# LM393_universal_breakout.net
KiCad netlist of a schematic drawn in EAGLE
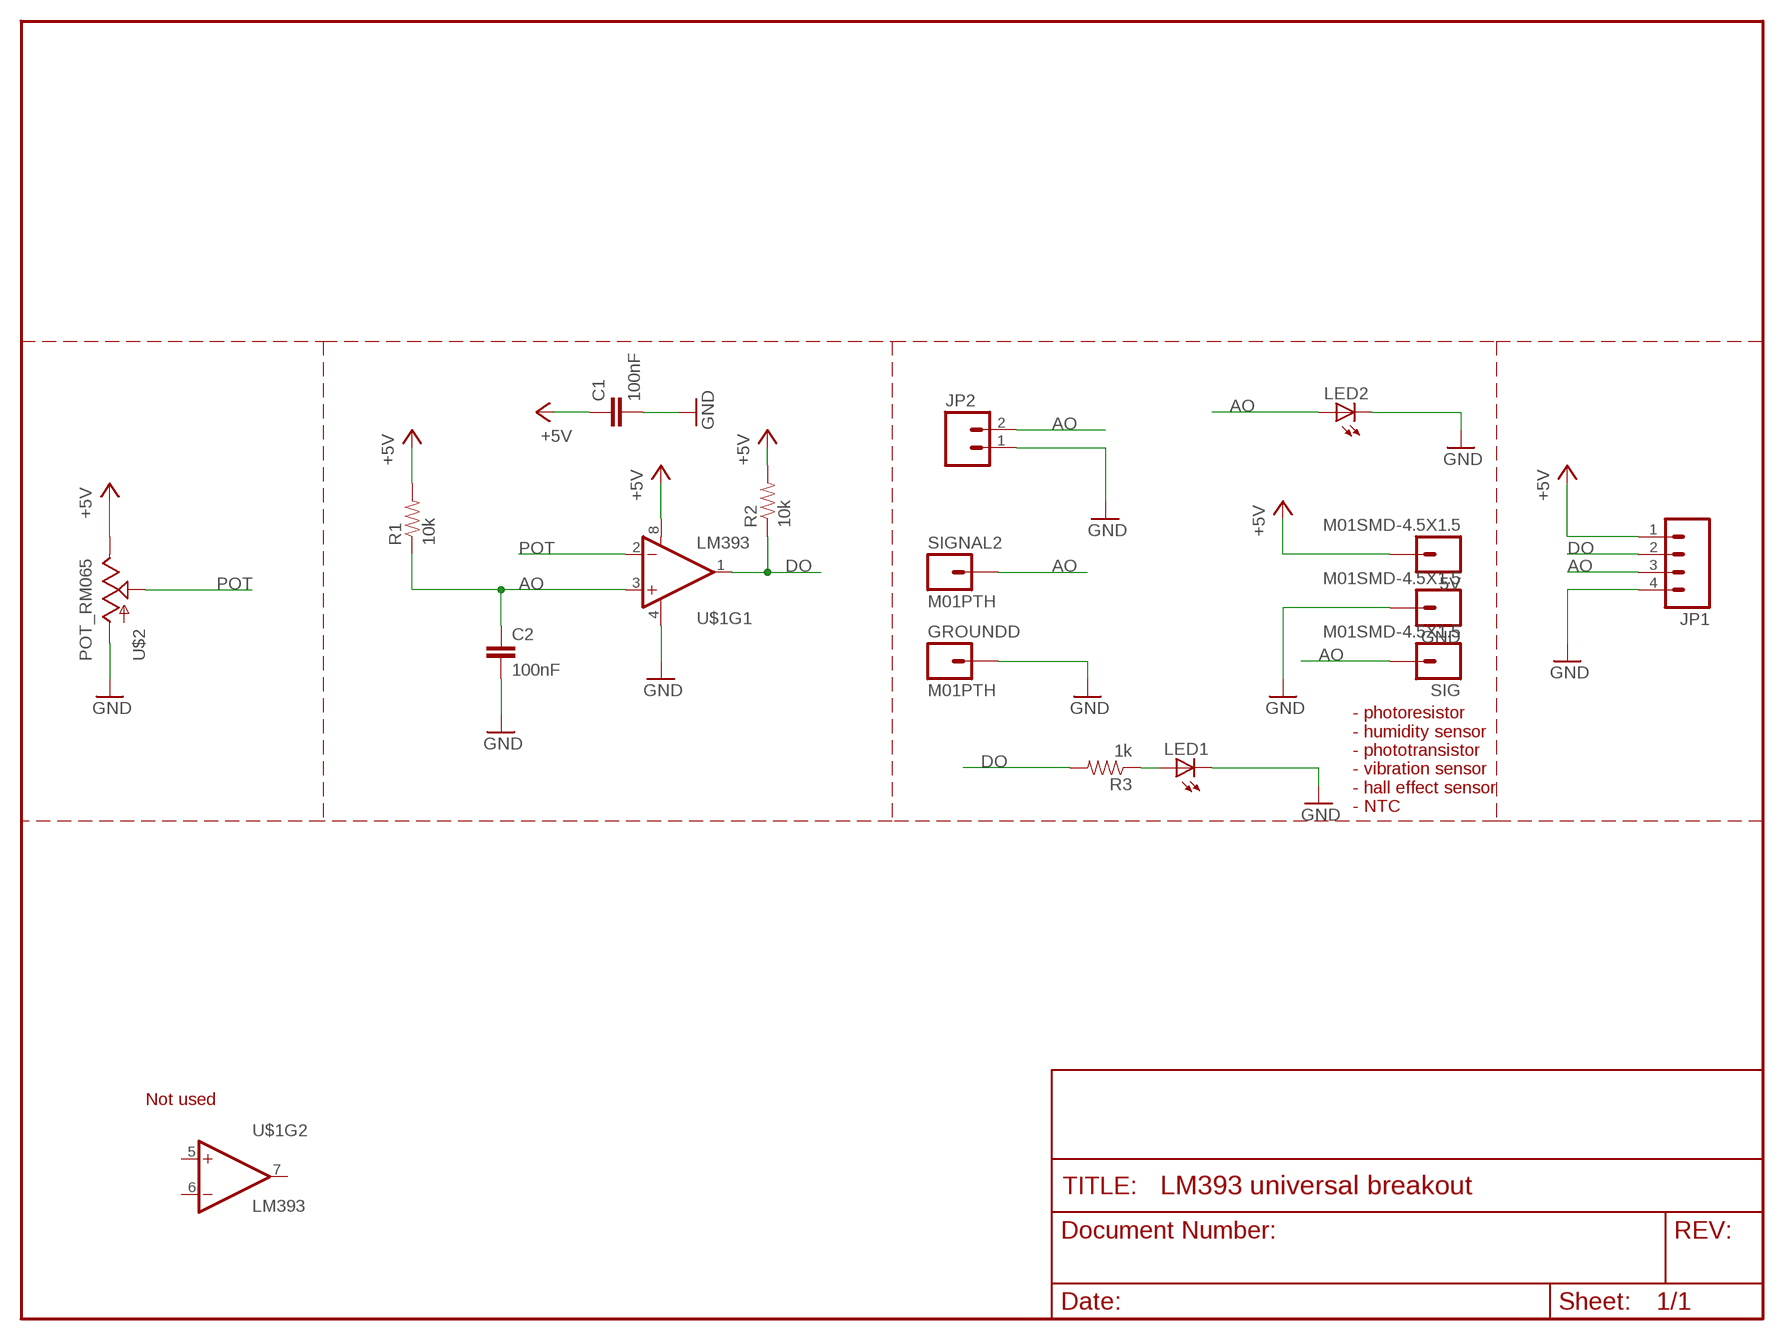
[diagram p0: schematic, sheet 1]

(export (version "E")
  (design (tool "Eeschema 10.0.6"))
  (components
    (comp (ref "5V")
      (value "M01SMD-4.5X1.5")
      (footprint "eagle-import:PAD-1.5X4.5")
      (libsource (lib "eagle-import") (part "M01SMD-4.5X1.5"))
    )
    (comp (ref "C1")
      (value "100nF")
      (footprint "eagle-import:0603-CAP")
      (libsource (lib "eagle-import") (part "CAP0603-CAP"))
    )
    (comp (ref "C2")
      (value "100nF")
      (footprint "eagle-import:0603-CAP")
      (libsource (lib "eagle-import") (part "CAP0603-CAP"))
    )
    (comp (ref "GND")
      (value "M01SMD-4.5X1.5")
      (footprint "eagle-import:PAD-1.5X4.5")
      (libsource (lib "eagle-import") (part "M01SMD-4.5X1.5"))
    )
    (comp (ref "GROUNDD")
      (value "M01PTH")
      (footprint "eagle-import:1X01")
      (libsource (lib "eagle-import") (part "M01PTH"))
    )
    (comp (ref "JP1")
      (value "M04PTH")
      (footprint "eagle-import:1X04")
      (libsource (lib "eagle-import") (part "M04PTH"))
    )
    (comp (ref "JP2")
      (value "M02PTH")
      (footprint "eagle-import:1X02")
      (libsource (lib "eagle-import") (part "M02PTH"))
    )
    (comp (ref "LED1")
      (value "LEDCHIP-LED0805")
      (footprint "eagle-import:CHIP-LED0805")
      (libsource (lib "eagle-import") (part "LEDCHIP-LED0805"))
    )
    (comp (ref "LED2")
      (value "LED5MM")
      (footprint "eagle-import:LED5MM")
      (libsource (lib "eagle-import") (part "LED5MM"))
    )
    (comp (ref "R1")
      (value "10k")
      (footprint "eagle-import:0603-RES")
      (libsource (lib "eagle-import") (part "RESISTOR0603-RES"))
    )
    (comp (ref "R2")
      (value "10k")
      (footprint "eagle-import:0603-RES")
      (libsource (lib "eagle-import") (part "RESISTOR0603-RES"))
    )
    (comp (ref "R3")
      (value "1k")
      (footprint "eagle-import:0603-RES")
      (libsource (lib "eagle-import") (part "RESISTOR0603-RES"))
    )
    (comp (ref "SIG")
      (value "M01SMD-4.5X1.5")
      (footprint "eagle-import:PAD-1.5X4.5")
      (libsource (lib "eagle-import") (part "M01SMD-4.5X1.5"))
    )
    (comp (ref "SIGNAL2")
      (value "M01PTH")
      (footprint "eagle-import:1X01")
      (libsource (lib "eagle-import") (part "M01PTH"))
    )
    (comp (ref "U$1")
      (value "LM393")
      (footprint "eagle-import:SO08")
      (libsource (lib "eagle-import") (part "LM393"))
    )
    (comp (ref "U$2")
      (value "POT_RM065")
      (footprint "eagle-import:RM065")
      (libsource (lib "eagle-import") (part "POT_RM065"))
    )
  )
  (nets
    (net (code "1") (name "+5V") (class "Default")
      (node (ref "5V") (pin "P$1") (pinfunction "1_P$1") (pintype "passive"))
      (node (ref "C1") (pin "1") (pinfunction "1_1") (pintype "passive"))
      (node (ref "JP1") (pin "1") (pinfunction "1_1") (pintype "passive"))
      (node (ref "R1") (pin "2") (pinfunction "2_2") (pintype "passive"))
      (node (ref "R2") (pin "2") (pinfunction "2_2") (pintype "passive"))
      (node (ref "U$1") (pin "8") (pinfunction "V+_8") (pintype "power_in"))
      (node (ref "U$2") (pin "3") (pinfunction "E_3") (pintype "passive"))
    )
    (net (code "2") (name "/AO") (class "Default")
      (node (ref "C2") (pin "1") (pinfunction "1_1") (pintype "passive"))
      (node (ref "JP1") (pin "3") (pinfunction "3_3") (pintype "passive"))
      (node (ref "JP2") (pin "2") (pinfunction "2_2") (pintype "passive"))
      (node (ref "LED2") (pin "A") (pinfunction "A_A") (pintype "passive"))
      (node (ref "R1") (pin "1") (pinfunction "1_1") (pintype "passive"))
      (node (ref "SIG") (pin "P$1") (pinfunction "1_P$1") (pintype "passive"))
      (node (ref "SIGNAL2") (pin "1") (pinfunction "1_1") (pintype "passive"))
      (node (ref "U$1") (pin "3") (pinfunction "+IN_3") (pintype "input"))
    )
    (net (code "3") (name "/DO") (class "Default")
      (node (ref "JP1") (pin "2") (pinfunction "2_2") (pintype "passive"))
      (node (ref "R2") (pin "1") (pinfunction "1_1") (pintype "passive"))
      (node (ref "R3") (pin "2") (pinfunction "2_2") (pintype "passive"))
      (node (ref "U$1") (pin "1") (pinfunction "OUT_1") (pintype "output"))
    )
    (net (code "4") (name "/POT") (class "Default")
      (node (ref "U$1") (pin "2") (pinfunction "-IN_2") (pintype "input"))
      (node (ref "U$2") (pin "2") (pinfunction "S_2") (pintype "passive"))
    )
    (net (code "5") (name "GND") (class "Default")
      (node (ref "C1") (pin "2") (pinfunction "2_2") (pintype "passive"))
      (node (ref "C2") (pin "2") (pinfunction "2_2") (pintype "passive"))
      (node (ref "GND") (pin "P$1") (pinfunction "1_P$1") (pintype "passive"))
      (node (ref "GROUNDD") (pin "1") (pinfunction "1_1") (pintype "passive"))
      (node (ref "JP1") (pin "4") (pinfunction "4_4") (pintype "passive"))
      (node (ref "JP2") (pin "1") (pinfunction "1_1") (pintype "passive"))
      (node (ref "LED1") (pin "C") (pinfunction "C_C") (pintype "passive"))
      (node (ref "LED2") (pin "K") (pinfunction "C_K") (pintype "passive"))
      (node (ref "U$1") (pin "4") (pinfunction "V-_4") (pintype "power_in"))
      (node (ref "U$2") (pin "1") (pinfunction "A_1") (pintype "passive"))
    )
    (net (code "6") (name "Net-(LED1-PadA)") (class "Default")
      (node (ref "LED1") (pin "A") (pinfunction "A_A") (pintype "passive"))
      (node (ref "R3") (pin "1") (pinfunction "1_1") (pintype "passive"))
    )
    (net (code "7") (name "unconnected-(U$1B-+IN-Pad5)") (class "Default")
      (node (ref "U$1") (pin "5") (pinfunction "+IN_5") (pintype "input"))
    )
    (net (code "8") (name "unconnected-(U$1B--IN-Pad6)") (class "Default")
      (node (ref "U$1") (pin "6") (pinfunction "-IN_6") (pintype "input"))
    )
    (net (code "9") (name "unconnected-(U$1B-OUT-Pad7)") (class "Default")
      (node (ref "U$1") (pin "7") (pinfunction "OUT_7") (pintype "output"))
    )
  )
)
